# LM74700.net
KiCad netlist of a schematic drawn in Altium Designer
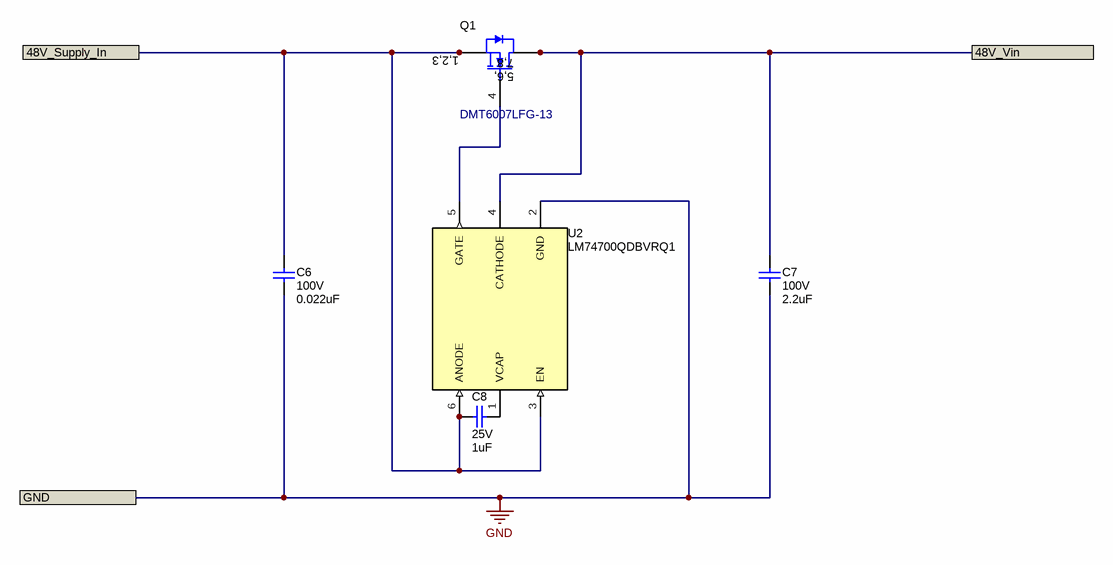
[diagram p0: LM74700.SchDoc]

(export (version "E")
  (design (tool "Eeschema 10.0.6"))
  (components
    (comp (ref "C6")
      (value "GRM21BR72A223KA01L")
      (footprint "0805_HV")
      (description "CAP, CERM, 0.022 uF, 100 V, +/- 10%, X7R, 0805")
      (fields
        (field (name "MANUFACTURER") "MuRata")
        (field (name "VDC_V") "100V")
        (field (name "VALUEDISPLAYED") "0.022uF")
        (field (name "PUBLISHER") "Texas Instruments")
      )
      (libsource (lib "Altium Vault - TI") (part "Capacitor"))
    )
    (comp (ref "C7")
      (value "GRM31CR72A225KA73L")
      (footprint "1206_190")
      (description "CAP, CERM, 2.2 uF, 100 V, +/- 10%, X7R, 1206_190")
      (fields
        (field (name "MANUFACTURER") "MuRata")
        (field (name "VDC_V") "100V")
        (field (name "VALUEDISPLAYED") "2.2uF")
        (field (name "PUBLISHER") "Texas Instruments")
      )
      (libsource (lib "Altium Vault - TI") (part "Capacitor"))
    )
    (comp (ref "C8")
      (value "GCM188R71E105KA64D")
      (footprint "0603")
      (description "CAP, CERM, 1 uF, 25 V, +/- 10%, X7R, AEC-Q200 Grade 1, 0603")
      (fields
        (field (name "MANUFACTURER") "MuRata")
        (field (name "VDC_V") "25V")
        (field (name "VALUEDISPLAYED") "1uF")
        (field (name "PUBLISHER") "Texas Instruments")
      )
      (libsource (lib "Altium Vault - TI") (part "Capacitor"))
    )
    (comp (ref "Q1")
      (value "DMT6007LFG-13")
      (footprint "PowerDI3333-8")
      (description "MOSFET, N-CH, 60 V, 15 A, AEC-Q101, 8-PowerVDFN")
      (fields (field (name "MANUFACTURER") "Diodes Inc.") (field (name "PUBLISHER") "Texas Instruments"))
      (libsource (lib "Altium Vault - TI") (part "MOSFET_N_D56789G4S123"))
    )
    (comp (ref "U2")
      (value "LM74700QDBVRQ1")
      (footprint "DBV0006A_N")
      (description "Low Iq Always ON Smart Diode Controller, DBV0006A (SOT-23-6)")
      (fields
        (field (name "ALTERNATE PARTNUMBER") "LM74700QDBVTQ1")
        (field (name "MANUFACTURER") "Texas Instruments")
        (field (name "PARTNUMBER") "LM74700QDBVRQ1")
      )
      (libsource (lib "Altium Vault - TI") (part "LM74700DDC"))
    )
  )
  (nets
    (net (code "1") (name "/48V_Supply_In") (class "Default")
      (node (ref "C6") (pin "1") (pinfunction "1_1") (pintype "passive"))
      (node (ref "C8") (pin "2") (pinfunction "2_2") (pintype "passive"))
      (node (ref "Q1") (pin "1") (pinfunction "S_1") (pintype "passive"))
      (node (ref "Q1") (pin "2") (pinfunction "S_2") (pintype "passive"))
      (node (ref "Q1") (pin "3") (pinfunction "S_3") (pintype "passive"))
      (node (ref "U2") (pin "3") (pinfunction "EN_3") (pintype "input"))
      (node (ref "U2") (pin "6") (pinfunction "ANODE_6") (pintype "input"))
    )
    (net (code "2") (name "/48V_Vin") (class "Default")
      (node (ref "C7") (pin "1") (pinfunction "1_1") (pintype "passive"))
      (node (ref "Q1") (pin "5") (pinfunction "D_5") (pintype "passive"))
      (node (ref "Q1") (pin "6") (pinfunction "D_6") (pintype "passive"))
      (node (ref "Q1") (pin "7") (pinfunction "D_7") (pintype "passive"))
      (node (ref "Q1") (pin "8") (pinfunction "D_8") (pintype "passive"))
      (node (ref "Q1") (pin "9") (pinfunction "D_9") (pintype "passive"))
      (node (ref "U2") (pin "4") (pinfunction "CATHODE_4") (pintype "power_in"))
    )
    (net (code "3") (name "GND") (class "Default")
      (node (ref "C6") (pin "2") (pinfunction "2_2") (pintype "passive"))
      (node (ref "C7") (pin "2") (pinfunction "2_2") (pintype "passive"))
      (node (ref "U2") (pin "2") (pinfunction "GND_2") (pintype "passive"))
    )
    (net (code "4") (name "Net-(Q1-G)") (class "Default")
      (node (ref "Q1") (pin "4") (pinfunction "G_4") (pintype "passive"))
      (node (ref "U2") (pin "5") (pinfunction "GATE_5") (pintype "output"))
    )
    (net (code "5") (name "Net-(U2-VCAP)") (class "Default")
      (node (ref "C8") (pin "1") (pinfunction "1_1") (pintype "passive"))
      (node (ref "U2") (pin "1") (pinfunction "VCAP_1") (pintype "power_in"))
    )
  )
)
